# TSAL-S01-V00-Control.net
KiCad netlist of a schematic drawn in Altium Designer
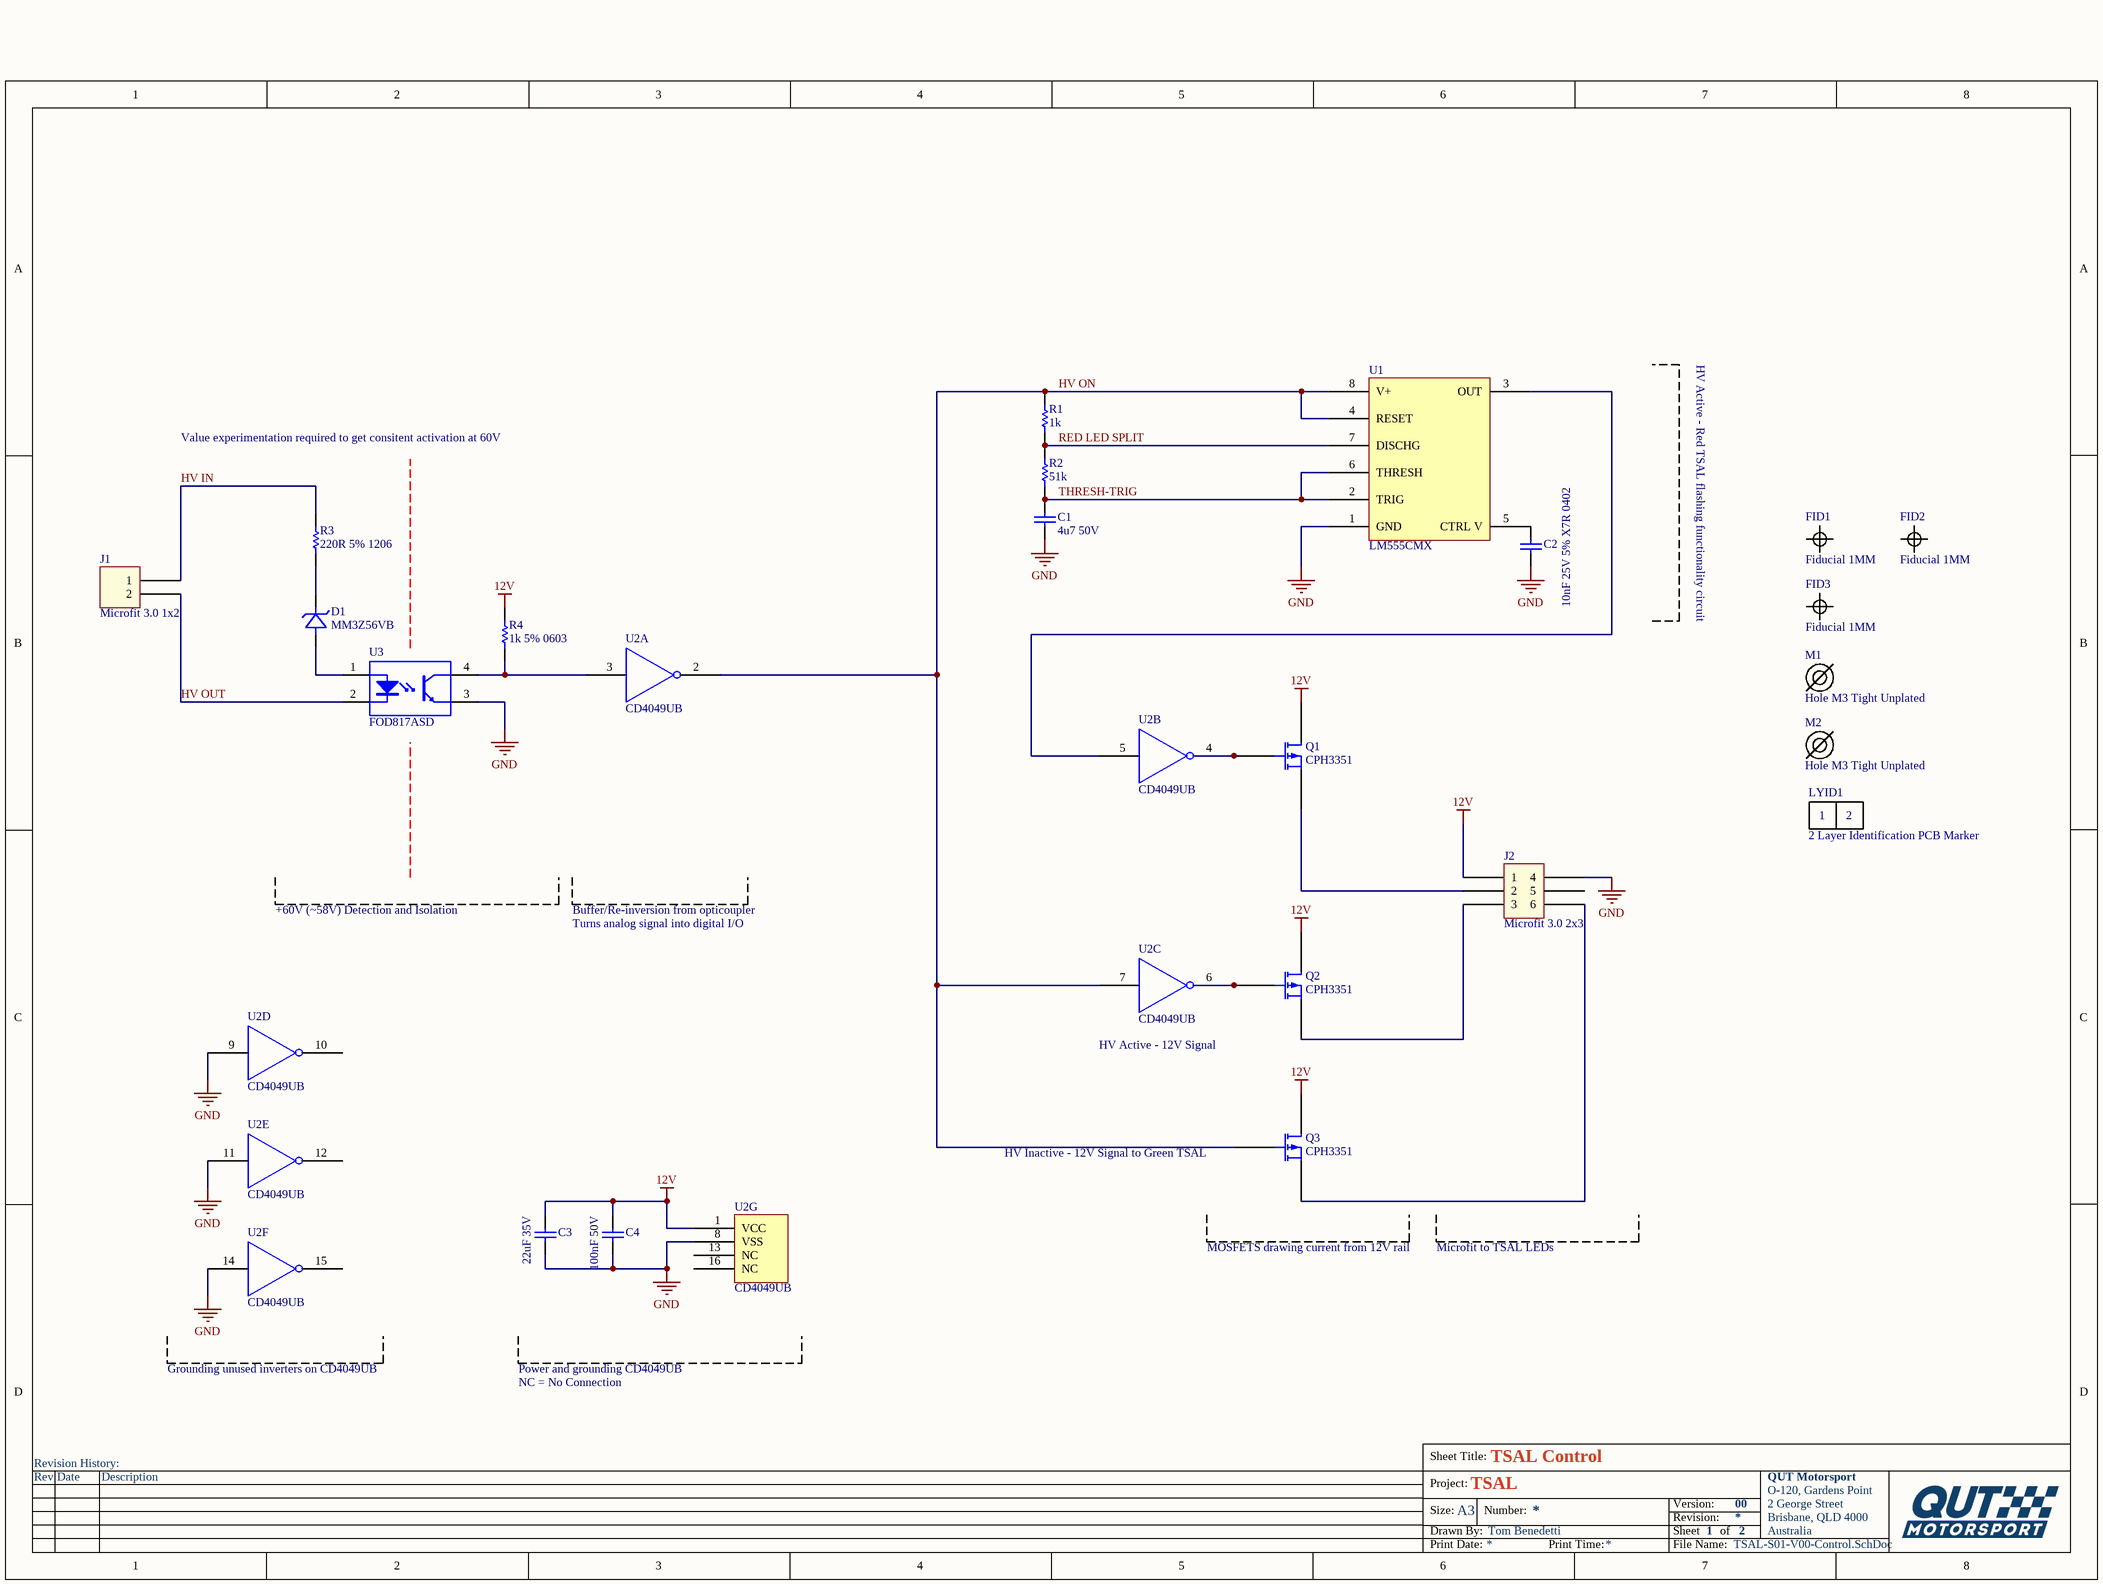
[diagram p0: TSAL-S01-V00-Control.SchDoc]

(export (version "E")
  (design (tool "Eeschema 10.0.6"))
  (components
    (comp (ref "C1")
      (value "4u7 50V")
      (footprint "Cap_Ceramic_0603")
      (description "Capacitor, Ceramic, SMD, 4u7, 50V, 5%, X7R, 0603")
      (libsource (lib "StandardCapacitors") (part "4u7 50V 5% X7R 0603"))
    )
    (comp (ref "C2")
      (value "10nF 25V 5% X7R 0402")
      (footprint "Cap_Ceramic_1206")
      (description "10000pF ±5% 25V Ceramic Capacitor X7R 0402 (1005 Metric)")
      (libsource (lib "StandardCapacitors") (part "10nF 25V 5% X7R 0402"))
    )
    (comp (ref "C3")
      (value "22uF 35V")
      (footprint "Cap_Ceramic_1206")
      (description "22µF ±20% 35V Ceramic Capacitor X5R 1206 (3216 Metric)")
      (libsource (lib "StandardCapacitors") (part "22uF 35V 20% X5R 1206"))
    )
    (comp (ref "C4")
      (value "100nF 50V")
      (footprint "Cap_Ceramic_0603")
      (description "Capacitor, Ceramic, SMD, 100nF, 50V, 5%, X7R, 0603")
      (libsource (lib "StandardCapacitors") (part "100nF 50V 5% X7R 0603"))
    )
    (comp (ref "D1")
      (value "MM3Z56VB")
      (footprint "SOD-323F")
      (description "Zener Diode 56V 200mW ±2% Surface Mount SOD-323F")
      (fields (field (name "MANUFACTURER") "ON Semiconductor"))
      (libsource (lib "QUTMS_DiodeLibrary") (part "MM3Z56VB"))
    )
    (comp (ref "FID1")
      (value "Fiducial 1MM")
      (footprint "FIDUCIAL 1MM")
      (libsource (lib "QUTMS_PCBLibrary") (part "Fiducial 1MM"))
    )
    (comp (ref "FID2")
      (value "Fiducial 1MM")
      (footprint "FIDUCIAL 1MM")
      (libsource (lib "QUTMS_PCBLibrary") (part "Fiducial 1MM"))
    )
    (comp (ref "FID3")
      (value "Fiducial 1MM")
      (footprint "FIDUCIAL 1MM")
      (libsource (lib "QUTMS_PCBLibrary") (part "Fiducial 1MM"))
    )
    (comp (ref "J1")
      (value "Microfit 3.0 1x2")
      (footprint "Microfit_1X2_R_TH")
      (libsource (lib "QUTMS_MicrofitLibrary") (part "Microfit_1x2"))
    )
    (comp (ref "J2")
      (value "Microfit 3.0 2x3")
      (footprint "Microfit_2X3_R_TH")
      (libsource (lib "QUTMS_MicrofitLibrary") (part "Microfit_2x3"))
    )
    (comp (ref "LYID1")
      (value "2 Layer Identification PCB Marker")
      (footprint "LAYER IDENT 2")
      (libsource (lib "QUTMS_PCBLibrary") (part "Layer Identification 2"))
    )
    (comp (ref "M1")
      (value "Hole M3 Tight Unplated")
      (footprint "M3.2 UNPLATED")
      (description "M3.2 Hole, No Plating")
      (libsource (lib "QUTMS_PCBLibrary") (part "Hole M3 Tight Unplated"))
    )
    (comp (ref "M2")
      (value "Hole M3 Tight Unplated")
      (footprint "M3.2 UNPLATED")
      (description "M3.2 Hole, No Plating")
      (libsource (lib "QUTMS_PCBLibrary") (part "Hole M3 Tight Unplated"))
    )
    (comp (ref "Q1")
      (value "CPH3351")
      (footprint "SOT-23-3")
      (description "P-Channel 60V 1.8A (Ta) 1W (Ta) Surface Mount 3-CPH")
      (libsource (lib "QUTMS_Transistors") (part "CPH3351"))
    )
    (comp (ref "Q2")
      (value "CPH3351")
      (footprint "SOT-23-3")
      (description "P-Channel 60V 1.8A (Ta) 1W (Ta) Surface Mount 3-CPH")
      (libsource (lib "QUTMS_Transistors") (part "CPH3351"))
    )
    (comp (ref "Q3")
      (value "CPH3351")
      (footprint "SOT-23-3")
      (description "P-Channel 60V 1.8A (Ta) 1W (Ta) Surface Mount 3-CPH")
      (libsource (lib "QUTMS_Transistors") (part "CPH3351"))
    )
    (comp (ref "R1")
      (value "1k")
      (footprint "Res_ThinFilm_0603")
      (description "Resistor, SMD, 1k, 0.1W, 5%, 0603")
      (libsource (lib "StandardResistors") (part "1k 5% 0603"))
    )
    (comp (ref "R2")
      (value "51k")
      (footprint "Res_ThinFilm_0603")
      (description "51 kOhms ±0.1% 0.063W, 1/16W Chip Resistor 0402 (1005 Metric) Automotive AEC-Q200 Thin Film")
      (libsource (lib "StandardResistors") (part "51k 5% 0603"))
    )
    (comp (ref "R3")
      (value "220R 5% 1206")
      (footprint "Res_ThinFilm_1206")
      (description "220 Ohms ±1% 0.25W, 1/4W Chip Resistor 1206 (3216 Metric) Moisture Resistant Thick Film")
      (libsource (lib "StandardResistors") (part "220R 5% 1206"))
    )
    (comp (ref "R4")
      (value "1k 5% 0603")
      (footprint "Res_ThinFilm_0603")
      (description "Resistor, SMD, 1k, 0.1W, 5%, 0603")
      (libsource (lib "StandardResistors") (part "1k 5% 0603"))
    )
    (comp (ref "U1")
      (value "LM555CMX")
      (footprint "MCP2561 SOIC")
      (description "555 Type, Timer/Oscillator (Single) IC 100kHz 8-SOIC")
      (libsource (lib "QUTMS_IntegratedCircuitLibrary") (part "LM555CMX"))
    )
    (comp (ref "U2")
      (value "CD4049UB")
      (footprint "CD4049UB")
      (libsource (lib "QUTMS_LogicLibrary") (part "CD4049UB"))
    )
    (comp (ref "U3")
      (value "FOD817ASD")
      (footprint "FOD817ASD")
      (description "Optoisolator 5kV Transistor 4SMD")
      (libsource (lib "QUTMS_OctocouplerLibrary") (part "FOD817ASD"))
    )
  )
  (nets
    (net (code "1") (name "/HV IN") (class "Default")
      (node (ref "J1") (pin "1") (pinfunction "1_1") (pintype "passive"))
      (node (ref "R3") (pin "2") (pinfunction "2_2") (pintype "passive"))
    )
    (net (code "2") (name "/HV ON") (class "Default")
      (node (ref "Q3") (pin "G") (pinfunction "G_G") (pintype "passive"))
      (node (ref "R1") (pin "2") (pinfunction "2_2") (pintype "passive"))
      (node (ref "U1") (pin "4") (pinfunction "RESET_4") (pintype "passive"))
      (node (ref "U1") (pin "8") (pinfunction "V+_8") (pintype "passive"))
      (node (ref "U2") (pin "2") (pinfunction "G_2") (pintype "passive"))
      (node (ref "U2") (pin "7") (pinfunction "C_7") (pintype "passive"))
    )
    (net (code "3") (name "/HV OUT") (class "Default")
      (node (ref "J1") (pin "2") (pinfunction "2_2") (pintype "passive"))
      (node (ref "U3") (pin "2") (pinfunction "CATHODE_2") (pintype "passive"))
    )
    (net (code "4") (name "/RED LED SPLIT") (class "Default")
      (node (ref "R1") (pin "1") (pinfunction "1_1") (pintype "passive"))
      (node (ref "R2") (pin "2") (pinfunction "2_2") (pintype "passive"))
      (node (ref "U1") (pin "7") (pinfunction "DISCHG_7") (pintype "passive"))
    )
    (net (code "5") (name "/THRESH-TRIG") (class "Default")
      (node (ref "C1") (pin "2") (pinfunction "2_2") (pintype "passive"))
      (node (ref "R2") (pin "1") (pinfunction "1_1") (pintype "passive"))
      (node (ref "U1") (pin "2") (pinfunction "TRIG_2") (pintype "passive"))
      (node (ref "U1") (pin "6") (pinfunction "THRESH_6") (pintype "passive"))
    )
    (net (code "6") (name "12V") (class "Default")
      (node (ref "C3") (pin "2") (pinfunction "2_2") (pintype "passive"))
      (node (ref "C4") (pin "2") (pinfunction "2_2") (pintype "passive"))
      (node (ref "J2") (pin "1") (pinfunction "1_1") (pintype "passive"))
      (node (ref "Q1") (pin "D") (pinfunction "D_D") (pintype "passive"))
      (node (ref "Q2") (pin "D") (pinfunction "D_D") (pintype "passive"))
      (node (ref "Q3") (pin "D") (pinfunction "D_D") (pintype "passive"))
      (node (ref "R4") (pin "2") (pinfunction "2_2") (pintype "passive"))
      (node (ref "U2") (pin "1") (pinfunction "VCC_1") (pintype "passive"))
    )
    (net (code "7") (name "GND") (class "Default")
      (node (ref "C1") (pin "1") (pinfunction "1_1") (pintype "passive"))
      (node (ref "C2") (pin "1") (pinfunction "1_1") (pintype "passive"))
      (node (ref "C3") (pin "1") (pinfunction "1_1") (pintype "passive"))
      (node (ref "C4") (pin "1") (pinfunction "1_1") (pintype "passive"))
      (node (ref "J2") (pin "4") (pinfunction "4_4") (pintype "passive"))
      (node (ref "U1") (pin "1") (pinfunction "GND_1") (pintype "passive"))
      (node (ref "U2") (pin "11") (pinfunction "E_11") (pintype "passive"))
      (node (ref "U2") (pin "14") (pinfunction "F_14") (pintype "passive"))
      (node (ref "U2") (pin "8") (pinfunction "VSS_8") (pintype "passive"))
      (node (ref "U2") (pin "9") (pinfunction "D_9") (pintype "passive"))
      (node (ref "U3") (pin "3") (pinfunction "EMITTER_3") (pintype "passive"))
    )
    (net (code "8") (name "Net-(D1-Anode)") (class "Default")
      (node (ref "D1") (pin "1") (pinfunction "Anode_1") (pintype "passive"))
      (node (ref "U3") (pin "1") (pinfunction "ANODE_1") (pintype "passive"))
    )
    (net (code "9") (name "Net-(D1-Cathode)") (class "Default")
      (node (ref "D1") (pin "2") (pinfunction "Cathode_2") (pintype "passive"))
      (node (ref "R3") (pin "1") (pinfunction "1_1") (pintype "passive"))
    )
    (net (code "10") (name "Net-(J2-Pad2)") (class "Default")
      (node (ref "J2") (pin "2") (pinfunction "2_2") (pintype "passive"))
      (node (ref "Q1") (pin "S") (pinfunction "S_S") (pintype "passive"))
    )
    (net (code "11") (name "Net-(J2-Pad3)") (class "Default")
      (node (ref "J2") (pin "3") (pinfunction "3_3") (pintype "passive"))
      (node (ref "Q2") (pin "S") (pinfunction "S_S") (pintype "passive"))
    )
    (net (code "12") (name "Net-(J2-Pad6)") (class "Default")
      (node (ref "J2") (pin "6") (pinfunction "6_6") (pintype "passive"))
      (node (ref "Q3") (pin "S") (pinfunction "S_S") (pintype "passive"))
    )
    (net (code "13") (name "Net-(U1-CTRL_V)") (class "Default")
      (node (ref "C2") (pin "2") (pinfunction "2_2") (pintype "passive"))
      (node (ref "U1") (pin "5") (pinfunction "CTRL_V_5") (pintype "passive"))
    )
    (net (code "14") (name "Net-(U1-OUT)") (class "Default")
      (node (ref "U1") (pin "3") (pinfunction "OUT_3") (pintype "passive"))
      (node (ref "U2") (pin "5") (pinfunction "B_5") (pintype "passive"))
    )
    (net (code "15") (name "Net-(U2A-A)") (class "Default")
      (node (ref "R4") (pin "1") (pinfunction "1_1") (pintype "passive"))
      (node (ref "U2") (pin "3") (pinfunction "A_3") (pintype "passive"))
      (node (ref "U3") (pin "4") (pinfunction "COLLECTOR_4") (pintype "passive"))
    )
    (net (code "16") (name "Net-(U2B-H)") (class "Default")
      (node (ref "Q1") (pin "G") (pinfunction "G_G") (pintype "passive"))
      (node (ref "U2") (pin "4") (pinfunction "H_4") (pintype "passive"))
    )
    (net (code "17") (name "Net-(U2C-I)") (class "Default")
      (node (ref "Q2") (pin "G") (pinfunction "G_G") (pintype "passive"))
      (node (ref "U2") (pin "6") (pinfunction "I_6") (pintype "passive"))
    )
    (net (code "18") (name "unconnected-(J2-Pad5)") (class "Default")
      (node (ref "J2") (pin "5") (pinfunction "5_5") (pintype "passive"))
    )
    (net (code "19") (name "unconnected-(U2D-J-Pad10)") (class "Default")
      (node (ref "U2") (pin "10") (pinfunction "J_10") (pintype "passive"))
    )
    (net (code "20") (name "unconnected-(U2E-K-Pad12)") (class "Default")
      (node (ref "U2") (pin "12") (pinfunction "K_12") (pintype "passive"))
    )
    (net (code "21") (name "unconnected-(U2F-L-Pad15)") (class "Default")
      (node (ref "U2") (pin "15") (pinfunction "L_15") (pintype "passive"))
    )
    (net (code "22") (name "unconnected-(U2G-NC-Pad13)") (class "Default")
      (node (ref "U2") (pin "13") (pinfunction "NC_13") (pintype "passive"))
    )
    (net (code "23") (name "unconnected-(U2G-NC-Pad16)") (class "Default")
      (node (ref "U2") (pin "16") (pinfunction "NC_16") (pintype "passive"))
    )
  )
)
